# Programmer.net
KiCad netlist of a schematic drawn in EAGLE
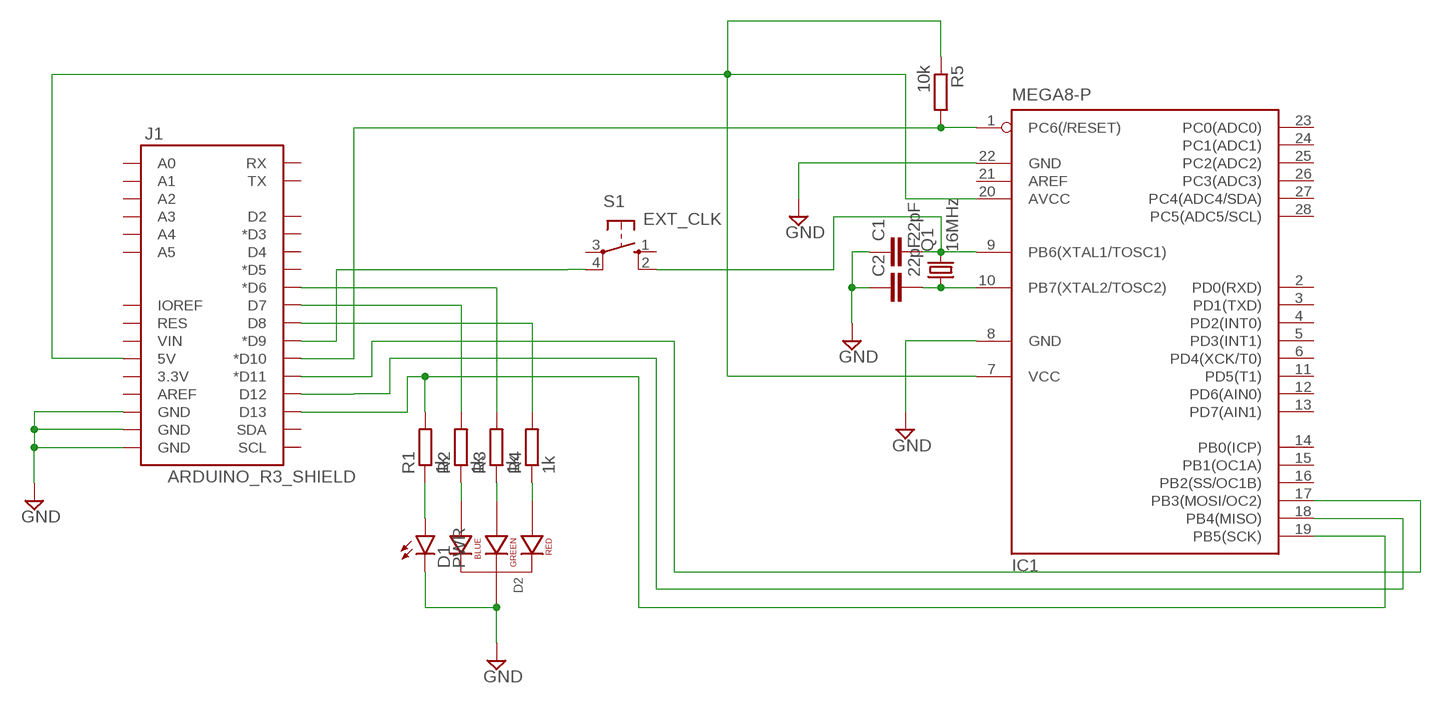
[diagram p0: schematic, sheet 1]

(export (version "E")
  (design (tool "Eeschema 10.0.6"))
  (components
    (comp (ref "C1")
      (value "22pF")
      (footprint "eagle-import:C5B2.5")
      (libsource (lib "eagle-import") (part "C5/2.5"))
    )
    (comp (ref "C2")
      (value "22pF")
      (footprint "eagle-import:C5B2.5")
      (libsource (lib "eagle-import") (part "C5/2.5"))
    )
    (comp (ref "D1")
      (value "PWR")
      (footprint "eagle-import:LED3MM")
      (libsource (lib "eagle-import") (part "LED3MM"))
    )
    (comp (ref "D2")
      (value "LED-RGB-CC-THRUCLEAR")
      (footprint "eagle-import:LED-RGB-THRU")
      (libsource (lib "eagle-import") (part "LED-RGB-CC-THRUCLEAR"))
    )
    (comp (ref "IC1")
      (value "MEGA8-P")
      (footprint "eagle-import:DIL28-3")
      (libsource (lib "eagle-import") (part "MEGA8-P"))
    )
    (comp (ref "J1")
      (value "ARDUINO_R3_SHIELD")
      (footprint "eagle-import:UNO_R3_SHIELD")
      (libsource (lib "eagle-import") (part "ARDUINO_R3_SHIELD"))
    )
    (comp (ref "Q1")
      (value "16MHz")
      (footprint "eagle-import:HC49_S")
      (libsource (lib "eagle-import") (part "CRYSTALHC49S"))
    )
    (comp (ref "R1")
      (value "1k")
      (footprint "eagle-import:0207_2V")
      (libsource (lib "eagle-import") (part "R-EU_0207_2V"))
    )
    (comp (ref "R2")
      (value "1k")
      (footprint "eagle-import:0207_2V")
      (libsource (lib "eagle-import") (part "R-EU_0207_2V"))
    )
    (comp (ref "R3")
      (value "1k")
      (footprint "eagle-import:0207_2V")
      (libsource (lib "eagle-import") (part "R-EU_0207_2V"))
    )
    (comp (ref "R4")
      (value "1k")
      (footprint "eagle-import:0207_2V")
      (libsource (lib "eagle-import") (part "R-EU_0207_2V"))
    )
    (comp (ref "R5")
      (value "10k")
      (footprint "eagle-import:0207_2V")
      (libsource (lib "eagle-import") (part "R-EU_0207_2V"))
    )
    (comp (ref "S1")
      (value "EXT_CLK")
      (footprint "eagle-import:B3F-10XX")
      (fields (field (name "MPN") "B3F-1000"))
      (libsource (lib "eagle-import") (part "10-XX"))
    )
  )
  (nets
    (net (code "1") (name "GND") (class "Default")
      (node (ref "C1") (pin "1") (pinfunction "1_1") (pintype "passive"))
      (node (ref "C2") (pin "1") (pinfunction "1_1") (pintype "passive"))
      (node (ref "D1") (pin "K") (pinfunction "C_K") (pintype "passive"))
      (node (ref "D2") (pin "2") (pinfunction "CATHODE_2") (pintype "bidirectional"))
      (node (ref "IC1") (pin "22") (pinfunction "GND_22") (pintype "power_in"))
      (node (ref "IC1") (pin "8") (pinfunction "GND_8") (pintype "power_in"))
      (node (ref "J1") (pin "GND@0") (pinfunction "GND_GND@0") (pintype "bidirectional"))
      (node (ref "J1") (pin "GND@1") (pinfunction "GND_GND@1") (pintype "bidirectional"))
      (node (ref "J1") (pin "GND@2") (pinfunction "GND_GND@2") (pintype "bidirectional"))
    )
    (net (code "2") (name "Net-(D1-PadA)") (class "Default")
      (node (ref "D1") (pin "A") (pinfunction "A_A") (pintype "passive"))
      (node (ref "R1") (pin "1") (pinfunction "1_1") (pintype "passive"))
    )
    (net (code "3") (name "Net-(D2-BLUE_CATHODE)") (class "Default")
      (node (ref "D2") (pin "4") (pinfunction "BLUE_CATHODE_4") (pintype "bidirectional"))
      (node (ref "R2") (pin "1") (pinfunction "1_1") (pintype "passive"))
    )
    (net (code "4") (name "Net-(D2-GREEN_CATHODE)") (class "Default")
      (node (ref "D2") (pin "3") (pinfunction "GREEN_CATHODE_3") (pintype "bidirectional"))
      (node (ref "R3") (pin "1") (pinfunction "1_1") (pintype "passive"))
    )
    (net (code "5") (name "Net-(D2-RED_CATHODE)") (class "Default")
      (node (ref "D2") (pin "1") (pinfunction "RED_CATHODE_1") (pintype "bidirectional"))
      (node (ref "R4") (pin "1") (pinfunction "1_1") (pintype "passive"))
    )
    (net (code "6") (name "Net-(IC1-AVCC)") (class "Default")
      (node (ref "IC1") (pin "20") (pinfunction "AVCC_20") (pintype "power_in"))
      (node (ref "IC1") (pin "7") (pinfunction "VCC_7") (pintype "power_in"))
      (node (ref "J1") (pin "5V") (pinfunction "5V_5V") (pintype "bidirectional"))
      (node (ref "R5") (pin "1") (pinfunction "1_1") (pintype "passive"))
    )
    (net (code "7") (name "Net-(IC1-PB3(MOSI{slash}OC2))") (class "Default")
      (node (ref "IC1") (pin "17") (pinfunction "PB3(MOSI/OC2)_17") (pintype "bidirectional"))
      (node (ref "J1") (pin "D11") (pinfunction "*D11_D11") (pintype "bidirectional"))
    )
    (net (code "8") (name "Net-(IC1-PB4(MISO))") (class "Default")
      (node (ref "IC1") (pin "18") (pinfunction "PB4(MISO)_18") (pintype "bidirectional"))
      (node (ref "J1") (pin "D12") (pinfunction "D12_D12") (pintype "bidirectional"))
    )
    (net (code "9") (name "Net-(IC1-PB5(SCK))") (class "Default")
      (node (ref "IC1") (pin "19") (pinfunction "PB5(SCK)_19") (pintype "bidirectional"))
      (node (ref "J1") (pin "D13") (pinfunction "D13_D13") (pintype "bidirectional"))
      (node (ref "R1") (pin "2") (pinfunction "2_2") (pintype "passive"))
    )
    (net (code "10") (name "Net-(IC1-PB6(XTAL1{slash}TOSC1))") (class "Default")
      (node (ref "C1") (pin "2") (pinfunction "2_2") (pintype "passive"))
      (node (ref "IC1") (pin "9") (pinfunction "PB6(XTAL1/TOSC1)_9") (pintype "bidirectional"))
      (node (ref "Q1") (pin "2") (pinfunction "2_2") (pintype "passive"))
      (node (ref "S1") (pin "2") (pinfunction "S1_2") (pintype "passive"))
    )
    (net (code "11") (name "Net-(IC1-PB7(XTAL2{slash}TOSC2))") (class "Default")
      (node (ref "C2") (pin "2") (pinfunction "2_2") (pintype "passive"))
      (node (ref "IC1") (pin "10") (pinfunction "PB7(XTAL2/TOSC2)_10") (pintype "bidirectional"))
      (node (ref "Q1") (pin "1") (pinfunction "1_1") (pintype "passive"))
    )
    (net (code "12") (name "Net-(IC1-PC6({slash}RESET))") (class "Default")
      (node (ref "IC1") (pin "1") (pinfunction "PC6(/RESET)_1") (pintype "bidirectional"))
      (node (ref "J1") (pin "D10") (pinfunction "*D10_D10") (pintype "bidirectional"))
      (node (ref "R5") (pin "2") (pinfunction "2_2") (pintype "passive"))
    )
    (net (code "13") (name "Net-(J1-*D6)") (class "Default")
      (node (ref "J1") (pin "D6") (pinfunction "*D6_D6") (pintype "bidirectional"))
      (node (ref "R3") (pin "2") (pinfunction "2_2") (pintype "passive"))
    )
    (net (code "14") (name "Net-(J1-*D9)") (class "Default")
      (node (ref "J1") (pin "D9") (pinfunction "*D9_D9") (pintype "bidirectional"))
      (node (ref "S1") (pin "4") (pinfunction "P1_4") (pintype "passive"))
    )
    (net (code "15") (name "Net-(J1-PadD7)") (class "Default")
      (node (ref "J1") (pin "D7") (pinfunction "D7_D7") (pintype "bidirectional"))
      (node (ref "R2") (pin "2") (pinfunction "2_2") (pintype "passive"))
    )
    (net (code "16") (name "Net-(J1-PadD8)") (class "Default")
      (node (ref "J1") (pin "D8") (pinfunction "D8_D8") (pintype "bidirectional"))
      (node (ref "R4") (pin "2") (pinfunction "2_2") (pintype "passive"))
    )
    (net (code "17") (name "unconnected-(IC1-AREF-Pad21)") (class "Default")
      (node (ref "IC1") (pin "21") (pinfunction "AREF_21") (pintype "passive"))
    )
    (net (code "18") (name "unconnected-(IC1-PB0(ICP)-Pad14)") (class "Default")
      (node (ref "IC1") (pin "14") (pinfunction "PB0(ICP)_14") (pintype "bidirectional"))
    )
    (net (code "19") (name "unconnected-(IC1-PB1(OC1A)-Pad15)") (class "Default")
      (node (ref "IC1") (pin "15") (pinfunction "PB1(OC1A)_15") (pintype "bidirectional"))
    )
    (net (code "20") (name "unconnected-(IC1-PB2(SS{slash}OC1B)-Pad16)") (class "Default")
      (node (ref "IC1") (pin "16") (pinfunction "PB2(SS/OC1B)_16") (pintype "bidirectional"))
    )
    (net (code "21") (name "unconnected-(IC1-PC0(ADC0)-Pad23)") (class "Default")
      (node (ref "IC1") (pin "23") (pinfunction "PC0(ADC0)_23") (pintype "bidirectional"))
    )
    (net (code "22") (name "unconnected-(IC1-PC1(ADC1)-Pad24)") (class "Default")
      (node (ref "IC1") (pin "24") (pinfunction "PC1(ADC1)_24") (pintype "bidirectional"))
    )
    (net (code "23") (name "unconnected-(IC1-PC2(ADC2)-Pad25)") (class "Default")
      (node (ref "IC1") (pin "25") (pinfunction "PC2(ADC2)_25") (pintype "bidirectional"))
    )
    (net (code "24") (name "unconnected-(IC1-PC3(ADC3)-Pad26)") (class "Default")
      (node (ref "IC1") (pin "26") (pinfunction "PC3(ADC3)_26") (pintype "bidirectional"))
    )
    (net (code "25") (name "unconnected-(IC1-PC4(ADC4{slash}SDA)-Pad27)") (class "Default")
      (node (ref "IC1") (pin "27") (pinfunction "PC4(ADC4/SDA)_27") (pintype "bidirectional"))
    )
    (net (code "26") (name "unconnected-(IC1-PC5(ADC5{slash}SCL)-Pad28)") (class "Default")
      (node (ref "IC1") (pin "28") (pinfunction "PC5(ADC5/SCL)_28") (pintype "bidirectional"))
    )
    (net (code "27") (name "unconnected-(IC1-PD0(RXD)-Pad2)") (class "Default")
      (node (ref "IC1") (pin "2") (pinfunction "PD0(RXD)_2") (pintype "bidirectional"))
    )
    (net (code "28") (name "unconnected-(IC1-PD1(TXD)-Pad3)") (class "Default")
      (node (ref "IC1") (pin "3") (pinfunction "PD1(TXD)_3") (pintype "bidirectional"))
    )
    (net (code "29") (name "unconnected-(IC1-PD2(INT0)-Pad4)") (class "Default")
      (node (ref "IC1") (pin "4") (pinfunction "PD2(INT0)_4") (pintype "bidirectional"))
    )
    (net (code "30") (name "unconnected-(IC1-PD3(INT1)-Pad5)") (class "Default")
      (node (ref "IC1") (pin "5") (pinfunction "PD3(INT1)_5") (pintype "bidirectional"))
    )
    (net (code "31") (name "unconnected-(IC1-PD4(XCK{slash}T0)-Pad6)") (class "Default")
      (node (ref "IC1") (pin "6") (pinfunction "PD4(XCK/T0)_6") (pintype "bidirectional"))
    )
    (net (code "32") (name "unconnected-(IC1-PD5(T1)-Pad11)") (class "Default")
      (node (ref "IC1") (pin "11") (pinfunction "PD5(T1)_11") (pintype "bidirectional"))
    )
    (net (code "33") (name "unconnected-(IC1-PD6(AIN0)-Pad12)") (class "Default")
      (node (ref "IC1") (pin "12") (pinfunction "PD6(AIN0)_12") (pintype "bidirectional"))
    )
    (net (code "34") (name "unconnected-(IC1-PD7(AIN1)-Pad13)") (class "Default")
      (node (ref "IC1") (pin "13") (pinfunction "PD7(AIN1)_13") (pintype "bidirectional"))
    )
    (net (code "35") (name "unconnected-(J1-*D3-PadD3)") (class "Default")
      (node (ref "J1") (pin "D3") (pinfunction "*D3_D3") (pintype "bidirectional"))
    )
    (net (code "36") (name "unconnected-(J1-*D5-PadD5)") (class "Default")
      (node (ref "J1") (pin "D5") (pinfunction "*D5_D5") (pintype "bidirectional"))
    )
    (net (code "37") (name "unconnected-(J1-Pad3.3V)") (class "Default")
      (node (ref "J1") (pin "3.3V") (pinfunction "3.3V_3.3V") (pintype "bidirectional"))
    )
    (net (code "38") (name "unconnected-(J1-PadA0)") (class "Default")
      (node (ref "J1") (pin "A0") (pinfunction "A0_A0") (pintype "bidirectional"))
    )
    (net (code "39") (name "unconnected-(J1-PadA1)") (class "Default")
      (node (ref "J1") (pin "A1") (pinfunction "A1_A1") (pintype "bidirectional"))
    )
    (net (code "40") (name "unconnected-(J1-PadA2)") (class "Default")
      (node (ref "J1") (pin "A2") (pinfunction "A2_A2") (pintype "bidirectional"))
    )
    (net (code "41") (name "unconnected-(J1-PadA3)") (class "Default")
      (node (ref "J1") (pin "A3") (pinfunction "A3_A3") (pintype "bidirectional"))
    )
    (net (code "42") (name "unconnected-(J1-PadA4)") (class "Default")
      (node (ref "J1") (pin "A4") (pinfunction "A4_A4") (pintype "bidirectional"))
    )
    (net (code "43") (name "unconnected-(J1-PadA5)") (class "Default")
      (node (ref "J1") (pin "A5") (pinfunction "A5_A5") (pintype "bidirectional"))
    )
    (net (code "44") (name "unconnected-(J1-PadAREF)") (class "Default")
      (node (ref "J1") (pin "AREF") (pinfunction "AREF_AREF") (pintype "bidirectional"))
    )
    (net (code "45") (name "unconnected-(J1-PadD2)") (class "Default")
      (node (ref "J1") (pin "D2") (pinfunction "D2_D2") (pintype "bidirectional"))
    )
    (net (code "46") (name "unconnected-(J1-PadD4)") (class "Default")
      (node (ref "J1") (pin "D4") (pinfunction "D4_D4") (pintype "bidirectional"))
    )
    (net (code "47") (name "unconnected-(J1-PadIOREF)") (class "Default")
      (node (ref "J1") (pin "IOREF") (pinfunction "IOREF_IOREF") (pintype "bidirectional"))
    )
    (net (code "48") (name "unconnected-(J1-PadRES)") (class "Default")
      (node (ref "J1") (pin "RES") (pinfunction "RES_RES") (pintype "bidirectional"))
    )
    (net (code "49") (name "unconnected-(J1-PadRX)") (class "Default")
      (node (ref "J1") (pin "RX") (pinfunction "RX_RX") (pintype "bidirectional"))
    )
    (net (code "50") (name "unconnected-(J1-PadSCL)") (class "Default")
      (node (ref "J1") (pin "SCL") (pinfunction "SCL_SCL") (pintype "bidirectional"))
    )
    (net (code "51") (name "unconnected-(J1-PadSDA)") (class "Default")
      (node (ref "J1") (pin "SDA") (pinfunction "SDA_SDA") (pintype "bidirectional"))
    )
    (net (code "52") (name "unconnected-(J1-PadTX)") (class "Default")
      (node (ref "J1") (pin "TX") (pinfunction "TX_TX") (pintype "bidirectional"))
    )
    (net (code "53") (name "unconnected-(J1-PadVIN)") (class "Default")
      (node (ref "J1") (pin "VIN") (pinfunction "VIN_VIN") (pintype "bidirectional"))
    )
    (net (code "54") (name "unconnected-(S1-P-Pad3)") (class "Default")
      (node (ref "S1") (pin "3") (pinfunction "P_3") (pintype "passive"))
    )
    (net (code "55") (name "unconnected-(S1-S-Pad1)") (class "Default")
      (node (ref "S1") (pin "1") (pinfunction "S_1") (pintype "passive"))
    )
  )
)
